# LED.net
KiCad netlist of a schematic drawn in Altium Designer
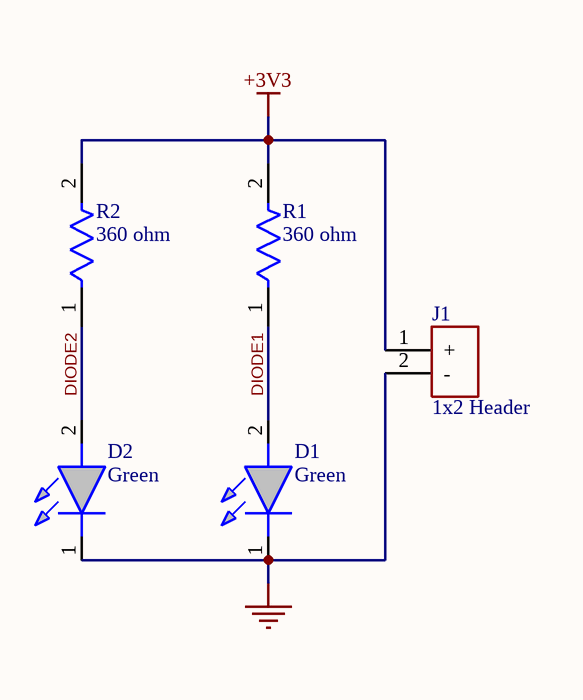
[diagram p0: LED.SchDoc]

(export (version "E")
  (design (tool "Eeschema 10.0.6"))
  (components
    (comp (ref "D1")
      (value "Green")
      (footprint "LED0603Green")
      (description "Standard LEDs - SMD SMD 0603 3V 1000mcd GREEN")
      (fields
        (field (name "MOUSER PART NUMBER") "593-LSM0603453V")
        (field (name "MANUFACTURER_PART_NUMBER") "LSM0603453V")
      )
      (libsource (lib "LED_LIB") (part "LSM0603453V"))
    )
    (comp (ref "D2")
      (value "Green")
      (footprint "LED0603Green")
      (description "Standard LEDs - SMD SMD 0603 3V 1000mcd GREEN")
      (fields
        (field (name "MOUSER PART NUMBER") "593-LSM0603453V")
        (field (name "MANUFACTURER_PART_NUMBER") "LSM0603453V")
      )
      (libsource (lib "LED_LIB") (part "LSM0603453V"))
    )
    (comp (ref "J1")
      (value "1x2 Header")
      (footprint "HDR1x2")
      (description "Conn Header Vert 2POS 2.54mm")
      (fields (field (name "MANUFACTURER") "Molex") (field (name "PARTNUMBER") "0022272021"))
      (libsource (lib "LED_LIB") (part "22-27-2021"))
    )
    (comp (ref "R1")
      (value "360 ohm")
      (footprint "R0805")
      (description "RES SMD 360 OHM 1% 1/8W 0805")
      (fields (field (name "TOLERANCE") "0.01") (field (name "MANUFACTURER") "Yageo"))
      (libsource (lib "LED_LIB") (part "CMP-03412-037214-1"))
    )
    (comp (ref "R2")
      (value "360 ohm")
      (footprint "R0805")
      (description "RES SMD 360 OHM 1% 1/8W 0805")
      (fields (field (name "TOLERANCE") "0.01") (field (name "MANUFACTURER") "Yageo"))
      (libsource (lib "LED_LIB") (part "CMP-03412-037214-1"))
    )
  )
  (nets
    (net (code "1") (name "+3V3") (class "Default")
      (node (ref "J1") (pin "1") (pinfunction "+_1") (pintype "passive"))
      (node (ref "R1") (pin "2") (pinfunction "2_2") (pintype "passive"))
      (node (ref "R2") (pin "2") (pinfunction "2_2") (pintype "passive"))
    )
    (net (code "2") (name "/DIODE1") (class "Default")
      (node (ref "D1") (pin "2") (pinfunction "A_2") (pintype "passive"))
      (node (ref "R1") (pin "1") (pinfunction "1_1") (pintype "passive"))
    )
    (net (code "3") (name "/DIODE2") (class "Default")
      (node (ref "D2") (pin "2") (pinfunction "A_2") (pintype "passive"))
      (node (ref "R2") (pin "1") (pinfunction "1_1") (pintype "passive"))
    )
    (net (code "4") (name "GND") (class "Default")
      (node (ref "D1") (pin "1") (pinfunction "K_1") (pintype "passive"))
      (node (ref "D2") (pin "1") (pinfunction "K_1") (pintype "passive"))
      (node (ref "J1") (pin "2") (pinfunction "-_2") (pintype "passive"))
    )
  )
)
